# hardware_ProjectFish.net
KiCad netlist of a schematic drawn in Altium Designer
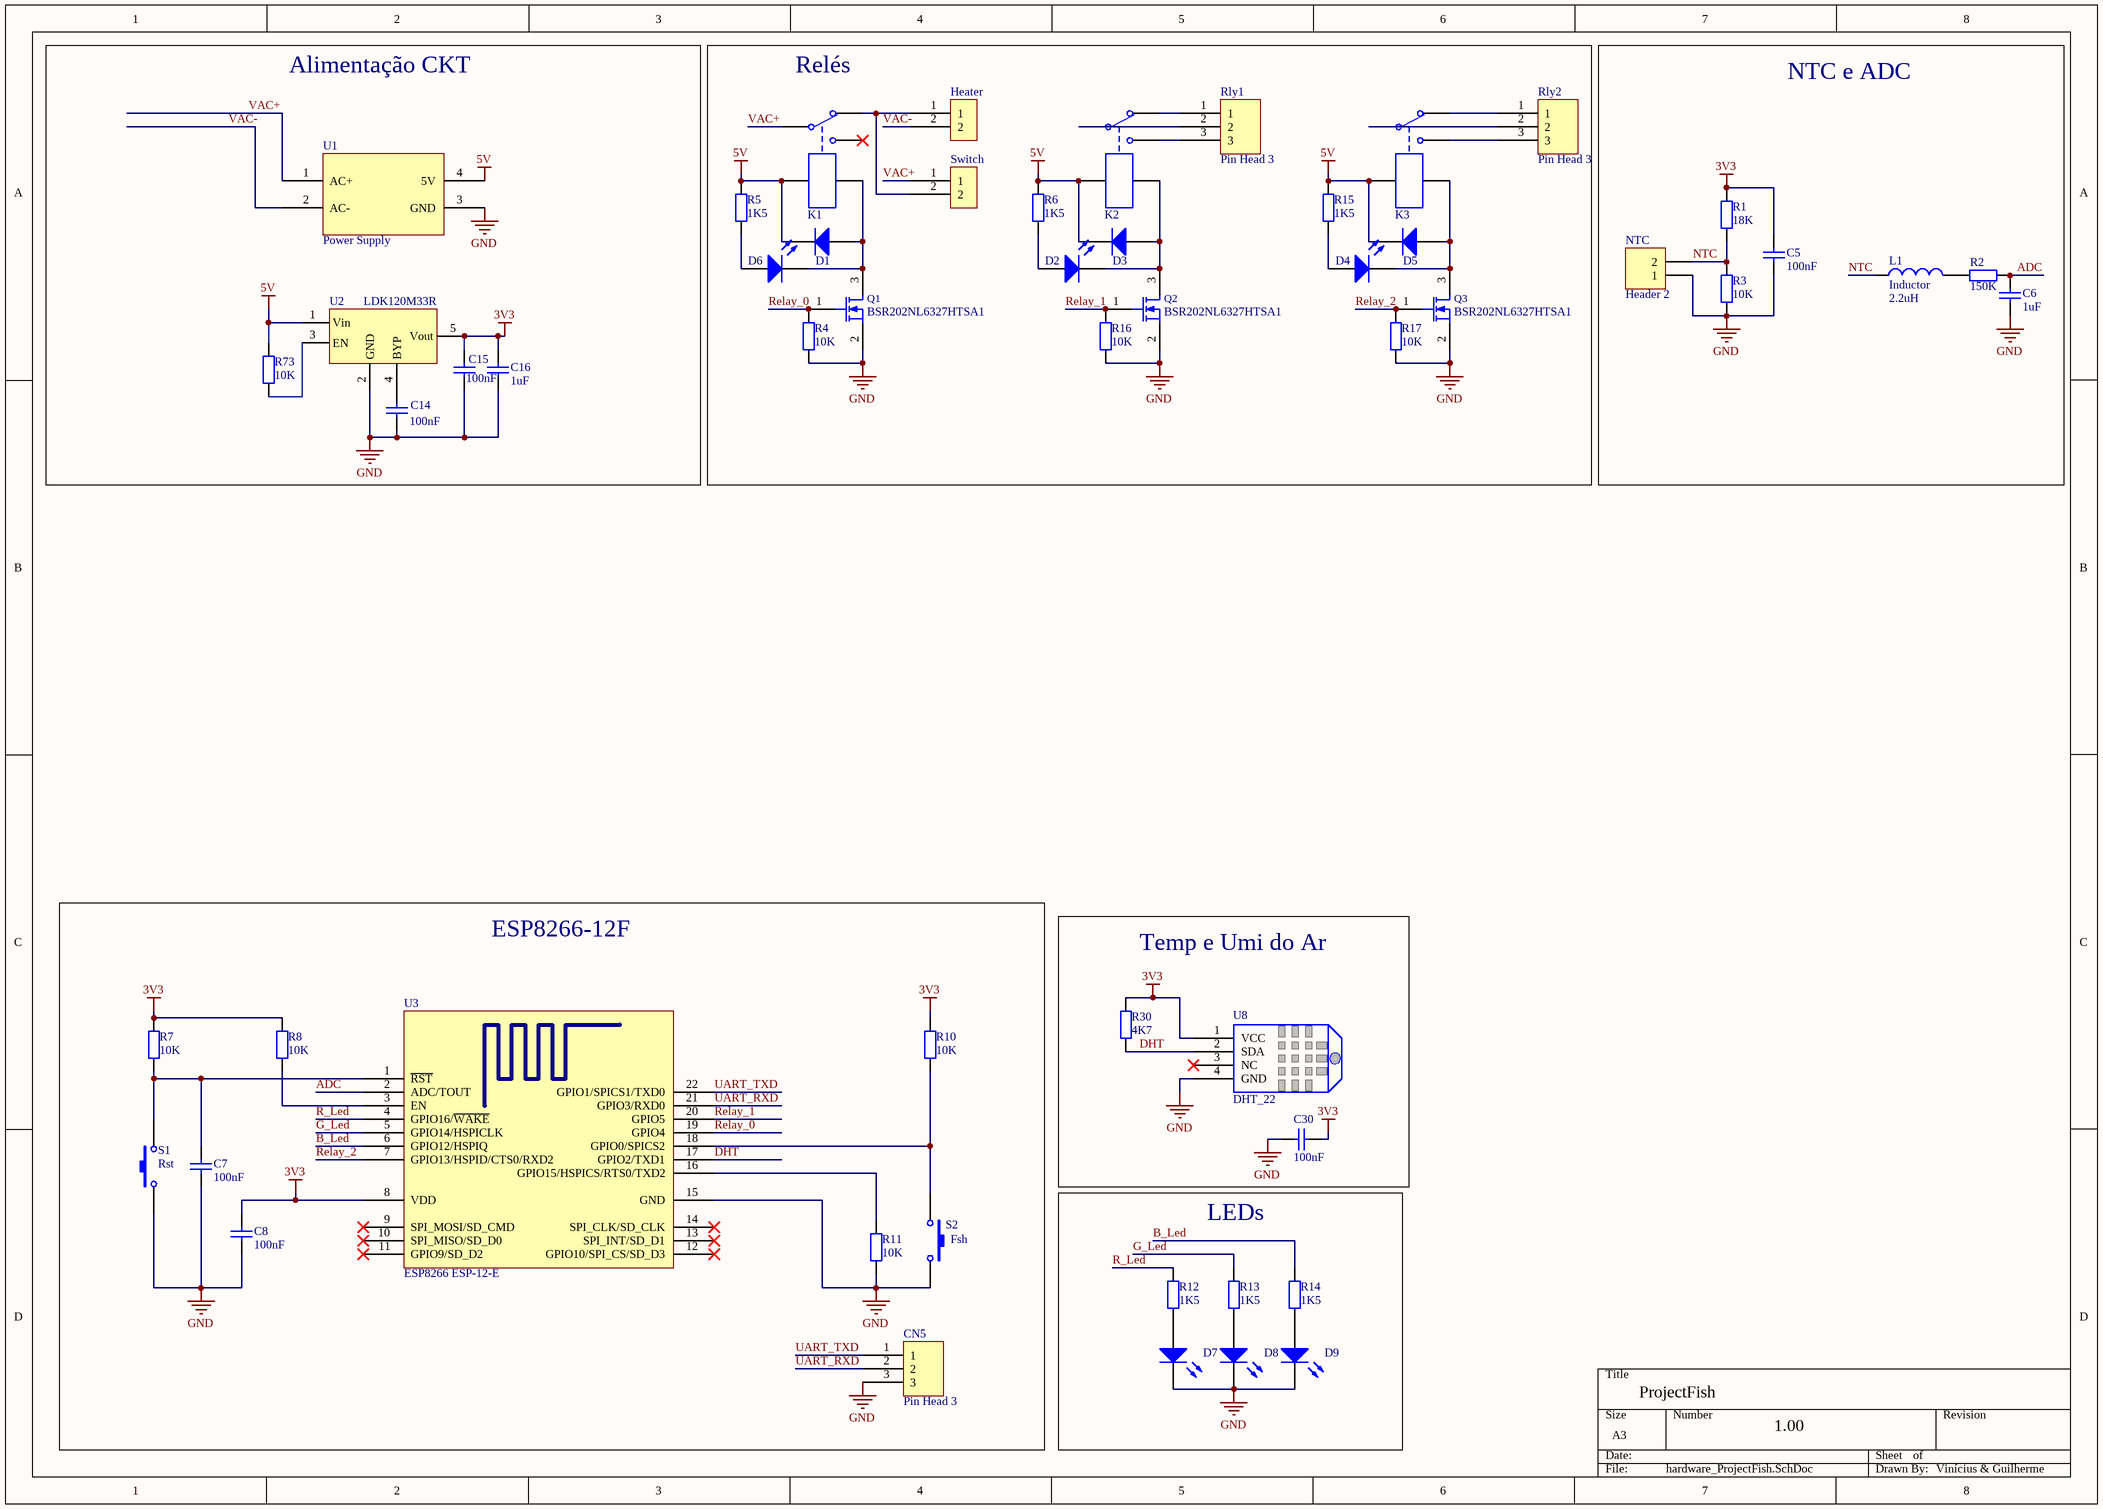
[diagram p0: hardware_ProjectFish.SchDoc]

(export (version "E")
  (design (tool "Eeschema 10.0.6"))
  (components
    (comp (ref "C5")
      (value "100nF")
      (footprint "0805 C")
      (description "Capacitor, ceramic, 100nF, 50V, 0805")
      (fields
        (field (name "PART NUMBER") "RK-cer-100nF-50V-0805")
        (field (name "Comment") "Cap-cer-100nF-50V-0805")
      )
      (libsource (lib "RAKS") (part "Cap-cer-100nF-50V-0805"))
    )
    (comp (ref "C6")
      (value "1uF")
      (footprint "0805 C")
      (description "Capacitor, ceramic, 1uF, 16V, 0805")
      (fields
        (field (name "PART NUMBER") "RK-cer-1uF-16V-0805")
        (field (name "Comment") "Cap-cer-1uF-16V-0805")
      )
      (libsource (lib "RAKS") (part "Cap-cer-1uF-16V-0805"))
    )
    (comp (ref "C7")
      (value "100nF")
      (footprint "0805 C")
      (description "Capacitor, ceramic, 100nF, 50V, 0805")
      (fields
        (field (name "PART NUMBER") "RK-cer-100nF-50V-0805")
        (field (name "Comment") "Cap-cer-100nF-50V-0805")
      )
      (libsource (lib "RAKS") (part "Cap-cer-100nF-50V-0805"))
    )
    (comp (ref "C8")
      (value "100nF")
      (footprint "0805 C")
      (description "Capacitor, ceramic, 100nF, 50V, 0805")
      (fields
        (field (name "PART NUMBER") "RK-cer-100nF-50V-0805")
        (field (name "Comment") "Cap-cer-100nF-50V-0805")
      )
      (libsource (lib "RAKS") (part "Cap-cer-100nF-50V-0805"))
    )
    (comp (ref "C14")
      (value "100nF")
      (footprint "0805 C")
      (description "Capacitor (Semiconductor SIM Model)")
      (fields (field (name "Comment") "Capacitor1") (field (name "PUBLISHER") "Altium Limited"))
      (libsource (lib "RAKS") (part "Capacitor1"))
    )
    (comp (ref "C15")
      (value "100nF")
      (footprint "0805 C")
      (description "Capacitor (Semiconductor SIM Model)")
      (fields (field (name "Comment") "Capacitor1") (field (name "PUBLISHER") "Altium Limited"))
      (libsource (lib "RAKS") (part "Capacitor1"))
    )
    (comp (ref "C16")
      (value "1uF")
      (footprint "0805 C")
      (description "Capacitor (Semiconductor SIM Model)")
      (fields (field (name "Comment") "Capacitor1") (field (name "PUBLISHER") "Altium Limited"))
      (libsource (lib "RAKS") (part "Capacitor1"))
    )
    (comp (ref "C30")
      (value "100nF")
      (footprint "0805 C")
      (description "Capacitor (Semiconductor SIM Model)")
      (fields (field (name "Comment") "Capacitor1") (field (name "PUBLISHER") "Altium Limited"))
      (libsource (lib "RAKS") (part "Capacitor1"))
    )
    (comp (ref "CN5")
      (value "Pin Head 3")
      (footprint "PIN HEAD 3")
      (libsource (lib "RAKS") (part "Pin Head 3"))
    )
    (comp (ref "D1")
      (value "Diode 1N4007")
      (footprint "DO-214AC")
      (description "1 Amp General Purpose Rectifier")
      (fields (field (name "PUBLISHER") "Altium Limited"))
      (libsource (lib "Miscellaneous Devices") (part "Diode 1N4007"))
    )
    (comp (ref "D2") (value "LED") (footprint "0805 LED") (libsource (lib "RAKS") (part "LED")))
    (comp (ref "D3")
      (value "Diode 1N4007")
      (footprint "DO-214AC")
      (description "1 Amp General Purpose Rectifier")
      (fields (field (name "PUBLISHER") "Altium Limited"))
      (libsource (lib "Miscellaneous Devices") (part "Diode 1N4007"))
    )
    (comp (ref "D4") (value "LED") (footprint "0805 LED") (libsource (lib "RAKS") (part "LED")))
    (comp (ref "D5")
      (value "Diode 1N4007")
      (footprint "DO-214AC")
      (description "1 Amp General Purpose Rectifier")
      (fields (field (name "PUBLISHER") "Altium Limited"))
      (libsource (lib "Miscellaneous Devices") (part "Diode 1N4007"))
    )
    (comp (ref "D6") (value "LED") (footprint "0805 LED") (libsource (lib "RAKS") (part "LED")))
    (comp (ref "D7") (value "LED") (footprint "0805 LED") (libsource (lib "RAKS") (part "LED")))
    (comp (ref "D8") (value "LED") (footprint "0805 LED") (libsource (lib "RAKS") (part "LED")))
    (comp (ref "D9") (value "LED") (footprint "0805 LED") (libsource (lib "RAKS") (part "LED")))
    (comp (ref "Heater")
      (value "Pin Head 2")
      (footprint "KRM mini")
      (libsource (lib "RAKS") (part "Pin Head 2"))
    )
    (comp (ref "K1") (value "Relay") (footprint "Relay") (libsource (lib "RAKS") (part "Relay")))
    (comp (ref "K2") (value "Relay") (footprint "Relay") (libsource (lib "RAKS") (part "Relay")))
    (comp (ref "K3") (value "Relay") (footprint "Relay") (libsource (lib "RAKS") (part "Relay")))
    (comp (ref "L1")
      (value "Inductor")
      (footprint "0805 R")
      (fields (field (name "ALTIUM_VALUE") "2.2uH") (field (name "PUBLISHER") "Altium Limited"))
      (libsource (lib "Miscellaneous Devices") (part "Inductor"))
    )
    (comp (ref "NTC")
      (value "Header 2")
      (footprint "HDR1X2")
      (description "Header, 2-Pin")
      (fields (field (name "PUBLISHER") "Altium Limited"))
      (libsource (lib "Miscellaneous Connectors") (part "Header 2"))
    )
    (comp (ref "Q1")
      (value "BSR202NL6327HTSA1")
      (footprint "BSR202NL")
      (description "N-Channel MOSFET")
      (fields (field (name "PUBLISHER") "Altium Limited"))
      (libsource (lib "RAKS") (part "MOSFET-N"))
    )
    (comp (ref "Q2")
      (value "BSR202NL6327HTSA1")
      (footprint "BSR202NL")
      (description "N-Channel MOSFET")
      (fields (field (name "PUBLISHER") "Altium Limited"))
      (libsource (lib "RAKS") (part "MOSFET-N"))
    )
    (comp (ref "Q3")
      (value "BSR202NL6327HTSA1")
      (footprint "BSR202NL")
      (description "N-Channel MOSFET")
      (fields (field (name "PUBLISHER") "Altium Limited"))
      (libsource (lib "RAKS") (part "MOSFET-N"))
    )
    (comp (ref "R1")
      (value "18K")
      (footprint "0805 R")
      (description "Resistor, 18K, 0805, 1%, 1/8W")
      (fields
        (field (name "PART NUMBER") "RK-18K-0805-1%-1/8W")
        (field (name "Comment") "Res-18K-0805-1%-1/8W")
      )
      (libsource (lib "RAKS") (part "Res-18K-0805-1%-1/8W"))
    )
    (comp (ref "R2")
      (value "150K")
      (footprint "0805 R")
      (description "Resistor, 150K, 0805, 1%, 1/8W")
      (fields
        (field (name "PART NUMBER") "RK-150K-0805-1%-1/8W")
        (field (name "Comment") "Res-150K-0805-1%-1/8W")
      )
      (libsource (lib "RAKS") (part "Res-150K-0805-1%-1/8W"))
    )
    (comp (ref "R3")
      (value "10K")
      (footprint "0805 R")
      (description "Resistor, 10K, 0805, 1%, 1/8W")
      (fields
        (field (name "PART NUMBER") "RK-10K-0805-1%-1/8W")
        (field (name "Comment") "Res-10K-0805-1%-1/8W")
      )
      (libsource (lib "RAKS") (part "Res-10K-0805-1%-1/8W"))
    )
    (comp (ref "R4")
      (value "10K")
      (footprint "0805 R")
      (description "Resistor, 10K, 0805, 1%, 1/8W")
      (fields
        (field (name "PART NUMBER") "RK-10K-0805-1%-1/8W")
        (field (name "Comment") "Res-10K-0805-1%-1/8W")
      )
      (libsource (lib "RAKS") (part "Res-10K-0805-1%-1/8W"))
    )
    (comp (ref "R5")
      (value "1K5")
      (footprint "0805 R")
      (description "Resistor, 1K8, 0805, 1%, 1/8W")
      (fields
        (field (name "PART NUMBER") "RK-1K8-0805-1%-1/8W")
        (field (name "Comment") "Res-1K8-0805-1%-1/8W")
      )
      (libsource (lib "RAKS") (part "Res-1K8-0805-1%-1/8W"))
    )
    (comp (ref "R6")
      (value "1K5")
      (footprint "0805 R")
      (description "Resistor, 1K8, 0805, 1%, 1/8W")
      (fields
        (field (name "PART NUMBER") "RK-1K8-0805-1%-1/8W")
        (field (name "Comment") "Res-1K8-0805-1%-1/8W")
      )
      (libsource (lib "RAKS") (part "Res-1K8-0805-1%-1/8W"))
    )
    (comp (ref "R7")
      (value "10K")
      (footprint "0805 R")
      (description "Resistor, 10K, 0805, 1%, 1/8W")
      (fields
        (field (name "PART NUMBER") "RK-10K-0805-1%-1/8W")
        (field (name "Comment") "Res-10K-0805-1%-1/8W")
      )
      (libsource (lib "RAKS") (part "Res-10K-0805-1%-1/8W"))
    )
    (comp (ref "R8")
      (value "10K")
      (footprint "0805 R")
      (description "Resistor, 10K, 0805, 1%, 1/8W")
      (fields
        (field (name "PART NUMBER") "RK-10K-0805-1%-1/8W")
        (field (name "Comment") "Res-10K-0805-1%-1/8W")
      )
      (libsource (lib "RAKS") (part "Res-10K-0805-1%-1/8W"))
    )
    (comp (ref "R10")
      (value "10K")
      (footprint "0805 R")
      (description "Resistor, 10K, 0805, 1%, 1/8W")
      (fields
        (field (name "PART NUMBER") "RK-10K-0805-1%-1/8W")
        (field (name "Comment") "Res-10K-0805-1%-1/8W")
      )
      (libsource (lib "RAKS") (part "Res-10K-0805-1%-1/8W"))
    )
    (comp (ref "R11")
      (value "10K")
      (footprint "0805 R")
      (description "Resistor, 10K, 0805, 1%, 1/8W")
      (fields
        (field (name "PART NUMBER") "RK-10K-0805-1%-1/8W")
        (field (name "Comment") "Res-10K-0805-1%-1/8W")
      )
      (libsource (lib "RAKS") (part "Res-10K-0805-1%-1/8W"))
    )
    (comp (ref "R12")
      (value "1K5")
      (footprint "0805 R")
      (description "Resistor, 1K,5 0805, 1%, 1/8W")
      (fields
        (field (name "PART NUMBER") "RK-1K5-0805-1%-1/8W")
        (field (name "Comment") "Res-1K5-0805-1%-1/8W")
      )
      (libsource (lib "RAKS") (part "Res-1K5-0805-1%-1/8W"))
    )
    (comp (ref "R13")
      (value "1K5")
      (footprint "0805 R")
      (description "Resistor, 1K,5 0805, 1%, 1/8W")
      (fields
        (field (name "PART NUMBER") "RK-1K5-0805-1%-1/8W")
        (field (name "Comment") "Res-1K5-0805-1%-1/8W")
      )
      (libsource (lib "RAKS") (part "Res-1K5-0805-1%-1/8W"))
    )
    (comp (ref "R14")
      (value "1K5")
      (footprint "0805 R")
      (description "Resistor, 1K,5 0805, 1%, 1/8W")
      (fields
        (field (name "PART NUMBER") "RK-1K5-0805-1%-1/8W")
        (field (name "Comment") "Res-1K5-0805-1%-1/8W")
      )
      (libsource (lib "RAKS") (part "Res-1K5-0805-1%-1/8W"))
    )
    (comp (ref "R15")
      (value "1K5")
      (footprint "0805 R")
      (description "Resistor, 1K8, 0805, 1%, 1/8W")
      (fields
        (field (name "PART NUMBER") "RK-1K8-0805-1%-1/8W")
        (field (name "Comment") "Res-1K8-0805-1%-1/8W")
      )
      (libsource (lib "RAKS") (part "Res-1K8-0805-1%-1/8W"))
    )
    (comp (ref "R16")
      (value "10K")
      (footprint "0805 R")
      (description "Resistor, 10K, 0805, 1%, 1/8W")
      (fields
        (field (name "PART NUMBER") "RK-10K-0805-1%-1/8W")
        (field (name "Comment") "Res-10K-0805-1%-1/8W")
      )
      (libsource (lib "RAKS") (part "Res-10K-0805-1%-1/8W"))
    )
    (comp (ref "R17")
      (value "10K")
      (footprint "0805 R")
      (description "Resistor, 10K, 0805, 1%, 1/8W")
      (fields
        (field (name "PART NUMBER") "RK-10K-0805-1%-1/8W")
        (field (name "Comment") "Res-10K-0805-1%-1/8W")
      )
      (libsource (lib "RAKS") (part "Res-10K-0805-1%-1/8W"))
    )
    (comp (ref "R30")
      (value "4K7")
      (footprint "0805 R")
      (description "Resistor")
      (fields (field (name "Comment") "Resistor1") (field (name "PUBLISHER") "Altium Limited"))
      (libsource (lib "RAKS") (part "Resistor1"))
    )
    (comp (ref "R73")
      (value "10K")
      (footprint "0805 R")
      (description "Resistor")
      (fields (field (name "Comment") "Resistor1") (field (name "PUBLISHER") "Altium Limited"))
      (libsource (lib "RAKS") (part "Resistor1"))
    )
    (comp (ref "Rly1") (value "Pin Head 3") (footprint "KRM 3") (libsource (lib "RAKS") (part "Pin Head 3")))
    (comp (ref "Rly2") (value "Pin Head 3") (footprint "KRM 3") (libsource (lib "RAKS") (part "Pin Head 3")))
    (comp (ref "S1")
      (value "Rst")
      (footprint "Button_SMD")
      (description "Switch NA")
      (libsource (lib "RAKS") (part "SW-PB"))
    )
    (comp (ref "S2")
      (value "Fsh")
      (footprint "Button_SMD")
      (description "Switch NA")
      (libsource (lib "RAKS") (part "SW-PB"))
    )
    (comp (ref "Switch")
      (value "Pin Head 2")
      (footprint "KRM mini")
      (libsource (lib "RAKS") (part "Pin Head 2"))
    )
    (comp (ref "U1")
      (value "Power Supply")
      (footprint "Sanmim SM-PLF12B")
      (description "AC/DC switch 5V@2A power supply")
      (libsource (lib "RAKS") (part "SANMIM SM-PLF12B"))
    )
    (comp (ref "U2")
      (value "LDK120M33R")
      (footprint "SOT-23-5")
      (description "Voltage Regulator")
      (libsource (lib "RAKS") (part "LDK120M33R"))
    )
    (comp (ref "U3")
      (value "ESP8266 ESP-12-E")
      (footprint "RAKS:ESP8266 ESP-12-E")
      (libsource (lib "RAKS") (part "ESP8266 ESP-12-E"))
    )
    (comp (ref "U8") (value "DHT_22") (footprint "Pin Head 4") (libsource (lib "RAKS") (part "DHT_22")))
  )
  (nets
    (net (code "1") (name "/ADC") (class "Default")
      (node (ref "C6") (pin "2") (pinfunction "2_2") (pintype "passive"))
      (node (ref "R2") (pin "2") (pinfunction "2_2") (pintype "passive"))
      (node (ref "U3") (pin "2") (pinfunction "ADC/TOUT_2") (pintype "passive"))
    )
    (net (code "2") (name "/B_Led") (class "Default")
      (node (ref "R14") (pin "2") (pinfunction "2_2") (pintype "passive"))
      (node (ref "U3") (pin "6") (pinfunction "GPIO12/HSPIQ_6") (pintype "passive"))
    )
    (net (code "3") (name "/DHT") (class "Default")
      (node (ref "R30") (pin "2") (pinfunction "2_2") (pintype "passive"))
      (node (ref "U3") (pin "17") (pinfunction "GPIO2/TXD1_17") (pintype "passive"))
      (node (ref "U8") (pin "2") (pinfunction "SDA_2") (pintype "passive"))
    )
    (net (code "4") (name "/G_Led") (class "Default")
      (node (ref "R13") (pin "2") (pinfunction "2_2") (pintype "passive"))
      (node (ref "U3") (pin "5") (pinfunction "GPIO14/HSPICLK_5") (pintype "passive"))
    )
    (net (code "5") (name "/NTC") (class "Default")
      (node (ref "L1") (pin "1") (pinfunction "1_1") (pintype "passive"))
      (node (ref "NTC") (pin "2") (pinfunction "2_2") (pintype "passive"))
      (node (ref "R1") (pin "1") (pinfunction "1_1") (pintype "passive"))
      (node (ref "R3") (pin "2") (pinfunction "2_2") (pintype "passive"))
    )
    (net (code "6") (name "/R_Led") (class "Default")
      (node (ref "R12") (pin "2") (pinfunction "2_2") (pintype "passive"))
      (node (ref "U3") (pin "4") (pinfunction "GPIO16/~{WAKE}_4") (pintype "passive"))
    )
    (net (code "7") (name "/Relay_0") (class "Default")
      (node (ref "Q1") (pin "1") (pinfunction "G_1") (pintype "passive"))
      (node (ref "R4") (pin "2") (pinfunction "2_2") (pintype "passive"))
      (node (ref "U3") (pin "19") (pinfunction "GPIO4_19") (pintype "passive"))
    )
    (net (code "8") (name "/Relay_1") (class "Default")
      (node (ref "Q2") (pin "1") (pinfunction "G_1") (pintype "passive"))
      (node (ref "R16") (pin "2") (pinfunction "2_2") (pintype "passive"))
      (node (ref "U3") (pin "20") (pinfunction "GPIO5_20") (pintype "passive"))
    )
    (net (code "9") (name "/Relay_2") (class "Default")
      (node (ref "Q3") (pin "1") (pinfunction "G_1") (pintype "passive"))
      (node (ref "R17") (pin "2") (pinfunction "2_2") (pintype "passive"))
      (node (ref "U3") (pin "7") (pinfunction "GPIO13/HSPID/CTS0/RXD2_7") (pintype "passive"))
    )
    (net (code "10") (name "/UART_RXD") (class "Default")
      (node (ref "CN5") (pin "2") (pinfunction "2_2") (pintype "passive"))
      (node (ref "U3") (pin "21") (pinfunction "GPIO3/RXD0_21") (pintype "passive"))
    )
    (net (code "11") (name "/UART_TXD") (class "Default")
      (node (ref "CN5") (pin "1") (pinfunction "1_1") (pintype "passive"))
      (node (ref "U3") (pin "22") (pinfunction "GPIO1/SPICS1/TXD0_22") (pintype "passive"))
    )
    (net (code "12") (name "/VAC+") (class "Default")
      (node (ref "K1") (pin "1") (pinfunction "1_1") (pintype "passive"))
      (node (ref "Switch") (pin "1") (pinfunction "1_1") (pintype "passive"))
      (node (ref "U1") (pin "1") (pinfunction "AC+_1") (pintype "passive"))
    )
    (net (code "13") (name "/VAC-") (class "Default")
      (node (ref "Heater") (pin "2") (pinfunction "2_2") (pintype "passive"))
      (node (ref "U1") (pin "2") (pinfunction "AC-_2") (pintype "passive"))
    )
    (net (code "14") (name "3V3") (class "Default")
      (node (ref "C15") (pin "2") (pinfunction "2_2") (pintype "passive"))
      (node (ref "C16") (pin "2") (pinfunction "2_2") (pintype "passive"))
      (node (ref "C30") (pin "2") (pinfunction "2_2") (pintype "passive"))
      (node (ref "C5") (pin "1") (pinfunction "1_1") (pintype "passive"))
      (node (ref "C8") (pin "1") (pinfunction "1_1") (pintype "passive"))
      (node (ref "R1") (pin "2") (pinfunction "2_2") (pintype "passive"))
      (node (ref "R10") (pin "2") (pinfunction "2_2") (pintype "passive"))
      (node (ref "R30") (pin "1") (pinfunction "1_1") (pintype "passive"))
      (node (ref "R7") (pin "2") (pinfunction "2_2") (pintype "passive"))
      (node (ref "R8") (pin "2") (pinfunction "2_2") (pintype "passive"))
      (node (ref "U2") (pin "5") (pinfunction "Vout_5") (pintype "passive"))
      (node (ref "U3") (pin "8") (pinfunction "VDD_8") (pintype "passive"))
      (node (ref "U8") (pin "1") (pinfunction "VCC_1") (pintype "passive"))
    )
    (net (code "15") (name "5V") (class "Default")
      (node (ref "D1") (pin "2") (pinfunction "K_2") (pintype "passive"))
      (node (ref "D3") (pin "2") (pinfunction "K_2") (pintype "passive"))
      (node (ref "D5") (pin "2") (pinfunction "K_2") (pintype "passive"))
      (node (ref "K1") (pin "4") (pinfunction "4_4") (pintype "passive"))
      (node (ref "K2") (pin "4") (pinfunction "4_4") (pintype "passive"))
      (node (ref "K3") (pin "4") (pinfunction "4_4") (pintype "passive"))
      (node (ref "R15") (pin "2") (pinfunction "2_2") (pintype "passive"))
      (node (ref "R5") (pin "2") (pinfunction "2_2") (pintype "passive"))
      (node (ref "R6") (pin "2") (pinfunction "2_2") (pintype "passive"))
      (node (ref "R73") (pin "1") (pinfunction "1_1") (pintype "passive"))
      (node (ref "U1") (pin "4") (pinfunction "5V_4") (pintype "passive"))
      (node (ref "U2") (pin "1") (pinfunction "Vin_1") (pintype "passive"))
    )
    (net (code "16") (name "GND") (class "Default")
      (node (ref "C14") (pin "1") (pinfunction "1_1") (pintype "passive"))
      (node (ref "C15") (pin "1") (pinfunction "1_1") (pintype "passive"))
      (node (ref "C16") (pin "1") (pinfunction "1_1") (pintype "passive"))
      (node (ref "C30") (pin "1") (pinfunction "1_1") (pintype "passive"))
      (node (ref "C5") (pin "2") (pinfunction "2_2") (pintype "passive"))
      (node (ref "C6") (pin "1") (pinfunction "1_1") (pintype "passive"))
      (node (ref "C7") (pin "1") (pinfunction "1_1") (pintype "passive"))
      (node (ref "C8") (pin "2") (pinfunction "2_2") (pintype "passive"))
      (node (ref "CN5") (pin "3") (pinfunction "3_3") (pintype "passive"))
      (node (ref "D7") (pin "2") (pinfunction "K_2") (pintype "passive"))
      (node (ref "D8") (pin "2") (pinfunction "K_2") (pintype "passive"))
      (node (ref "D9") (pin "2") (pinfunction "K_2") (pintype "passive"))
      (node (ref "NTC") (pin "1") (pinfunction "1_1") (pintype "passive"))
      (node (ref "Q1") (pin "2") (pinfunction "S_2") (pintype "passive"))
      (node (ref "Q2") (pin "2") (pinfunction "S_2") (pintype "passive"))
      (node (ref "Q3") (pin "2") (pinfunction "S_2") (pintype "passive"))
      (node (ref "R11") (pin "1") (pinfunction "1_1") (pintype "passive"))
      (node (ref "R16") (pin "1") (pinfunction "1_1") (pintype "passive"))
      (node (ref "R17") (pin "1") (pinfunction "1_1") (pintype "passive"))
      (node (ref "R3") (pin "1") (pinfunction "1_1") (pintype "passive"))
      (node (ref "R4") (pin "1") (pinfunction "1_1") (pintype "passive"))
      (node (ref "S1") (pin "1") (pinfunction "1_1") (pintype "passive"))
      (node (ref "S2") (pin "1") (pinfunction "1_1") (pintype "passive"))
      (node (ref "U1") (pin "3") (pinfunction "GND_3") (pintype "passive"))
      (node (ref "U2") (pin "2") (pinfunction "GND_2") (pintype "passive"))
      (node (ref "U3") (pin "15") (pinfunction "GND_15") (pintype "passive"))
      (node (ref "U8") (pin "4") (pinfunction "GND_4") (pintype "passive"))
    )
    (net (code "17") (name "Net-(D1-A)") (class "Default")
      (node (ref "D1") (pin "1") (pinfunction "A_1") (pintype "passive"))
      (node (ref "D6") (pin "2") (pinfunction "K_2") (pintype "passive"))
      (node (ref "K1") (pin "5") (pinfunction "5_5") (pintype "passive"))
      (node (ref "Q1") (pin "3") (pinfunction "D_3") (pintype "passive"))
    )
    (net (code "18") (name "Net-(D2-A)") (class "Default")
      (node (ref "D2") (pin "1") (pinfunction "A_1") (pintype "passive"))
      (node (ref "R6") (pin "1") (pinfunction "1_1") (pintype "passive"))
    )
    (net (code "19") (name "Net-(D2-K)") (class "Default")
      (node (ref "D2") (pin "2") (pinfunction "K_2") (pintype "passive"))
      (node (ref "D3") (pin "1") (pinfunction "A_1") (pintype "passive"))
      (node (ref "K2") (pin "5") (pinfunction "5_5") (pintype "passive"))
      (node (ref "Q2") (pin "3") (pinfunction "D_3") (pintype "passive"))
    )
    (net (code "20") (name "Net-(D4-A)") (class "Default")
      (node (ref "D4") (pin "1") (pinfunction "A_1") (pintype "passive"))
      (node (ref "R15") (pin "1") (pinfunction "1_1") (pintype "passive"))
    )
    (net (code "21") (name "Net-(D4-K)") (class "Default")
      (node (ref "D4") (pin "2") (pinfunction "K_2") (pintype "passive"))
      (node (ref "D5") (pin "1") (pinfunction "A_1") (pintype "passive"))
      (node (ref "K3") (pin "5") (pinfunction "5_5") (pintype "passive"))
      (node (ref "Q3") (pin "3") (pinfunction "D_3") (pintype "passive"))
    )
    (net (code "22") (name "Net-(D6-A)") (class "Default")
      (node (ref "D6") (pin "1") (pinfunction "A_1") (pintype "passive"))
      (node (ref "R5") (pin "1") (pinfunction "1_1") (pintype "passive"))
    )
    (net (code "23") (name "Net-(D7-A)") (class "Default")
      (node (ref "D7") (pin "1") (pinfunction "A_1") (pintype "passive"))
      (node (ref "R12") (pin "1") (pinfunction "1_1") (pintype "passive"))
    )
    (net (code "24") (name "Net-(D8-A)") (class "Default")
      (node (ref "D8") (pin "1") (pinfunction "A_1") (pintype "passive"))
      (node (ref "R13") (pin "1") (pinfunction "1_1") (pintype "passive"))
    )
    (net (code "25") (name "Net-(D9-A)") (class "Default")
      (node (ref "D9") (pin "1") (pinfunction "A_1") (pintype "passive"))
      (node (ref "R14") (pin "1") (pinfunction "1_1") (pintype "passive"))
    )
    (net (code "26") (name "Net-(Heater-Pad1)") (class "Default")
      (node (ref "Heater") (pin "1") (pinfunction "1_1") (pintype "passive"))
      (node (ref "K1") (pin "2") (pinfunction "2_2") (pintype "passive"))
      (node (ref "Switch") (pin "2") (pinfunction "2_2") (pintype "passive"))
    )
    (net (code "27") (name "Net-(K2-Pad1)") (class "Default")
      (node (ref "K2") (pin "1") (pinfunction "1_1") (pintype "passive"))
      (node (ref "Rly1") (pin "2") (pinfunction "2_2") (pintype "passive"))
    )
    (net (code "28") (name "Net-(K2-Pad2)") (class "Default")
      (node (ref "K2") (pin "2") (pinfunction "2_2") (pintype "passive"))
      (node (ref "Rly1") (pin "1") (pinfunction "1_1") (pintype "passive"))
    )
    (net (code "29") (name "Net-(K2-Pad3)") (class "Default")
      (node (ref "K2") (pin "3") (pinfunction "3_3") (pintype "passive"))
      (node (ref "Rly1") (pin "3") (pinfunction "3_3") (pintype "passive"))
    )
    (net (code "30") (name "Net-(K3-Pad1)") (class "Default")
      (node (ref "K3") (pin "1") (pinfunction "1_1") (pintype "passive"))
      (node (ref "Rly2") (pin "2") (pinfunction "2_2") (pintype "passive"))
    )
    (net (code "31") (name "Net-(K3-Pad2)") (class "Default")
      (node (ref "K3") (pin "2") (pinfunction "2_2") (pintype "passive"))
      (node (ref "Rly2") (pin "1") (pinfunction "1_1") (pintype "passive"))
    )
    (net (code "32") (name "Net-(K3-Pad3)") (class "Default")
      (node (ref "K3") (pin "3") (pinfunction "3_3") (pintype "passive"))
      (node (ref "Rly2") (pin "3") (pinfunction "3_3") (pintype "passive"))
    )
    (net (code "33") (name "Net-(L1-Pad2)") (class "Default")
      (node (ref "L1") (pin "2") (pinfunction "2_2") (pintype "passive"))
      (node (ref "R2") (pin "1") (pinfunction "1_1") (pintype "passive"))
    )
    (net (code "34") (name "Net-(U2-BYP)") (class "Default")
      (node (ref "C14") (pin "2") (pinfunction "2_2") (pintype "passive"))
      (node (ref "U2") (pin "4") (pinfunction "BYP_4") (pintype "passive"))
    )
    (net (code "35") (name "Net-(U2-EN)") (class "Default")
      (node (ref "R73") (pin "2") (pinfunction "2_2") (pintype "passive"))
      (node (ref "U2") (pin "3") (pinfunction "EN_3") (pintype "passive"))
    )
    (net (code "36") (name "Net-(U3-EN)") (class "Default")
      (node (ref "R8") (pin "1") (pinfunction "1_1") (pintype "passive"))
      (node (ref "U3") (pin "3") (pinfunction "EN_3") (pintype "passive"))
    )
    (net (code "37") (name "Net-(U3-GPIO0{slash}SPICS2)") (class "Default")
      (node (ref "R10") (pin "1") (pinfunction "1_1") (pintype "passive"))
      (node (ref "S2") (pin "2") (pinfunction "2_2") (pintype "passive"))
      (node (ref "U3") (pin "18") (pinfunction "GPIO0/SPICS2_18") (pintype "passive"))
    )
    (net (code "38") (name "Net-(U3-GPIO15{slash}HSPICS{slash}RTS0{slash}TXD2)") (class "Default")
      (node (ref "R11") (pin "2") (pinfunction "2_2") (pintype "passive"))
      (node (ref "U3") (pin "16") (pinfunction "GPIO15/HSPICS/RTS0/TXD2_16") (pintype "passive"))
    )
    (net (code "39") (name "Net-(U3-~{RST})") (class "Default")
      (node (ref "C7") (pin "2") (pinfunction "2_2") (pintype "passive"))
      (node (ref "R7") (pin "1") (pinfunction "1_1") (pintype "passive"))
      (node (ref "S1") (pin "2") (pinfunction "2_2") (pintype "passive"))
      (node (ref "U3") (pin "1") (pinfunction "~{RST}_1") (pintype "passive"))
    )
    (net (code "40") (name "unconnected-(K1-Pad3)") (class "Default")
      (node (ref "K1") (pin "3") (pinfunction "3_3") (pintype "passive+no_connect"))
    )
    (net (code "41") (name "unconnected-(U3-GPIO9{slash}SD_D2-Pad11)") (class "Default")
      (node (ref "U3") (pin "11") (pinfunction "GPIO9/SD_D2_11") (pintype "passive+no_connect"))
    )
    (net (code "42") (name "unconnected-(U3-GPIO10{slash}SPI_CS{slash}SD_D3-Pad12)") (class "Default")
      (node (ref "U3") (pin "12") (pinfunction "GPIO10/SPI_CS/SD_D3_12") (pintype "passive+no_connect"))
    )
    (net (code "43") (name "unconnected-(U3-SPI_CLK{slash}SD_CLK-Pad14)") (class "Default")
      (node (ref "U3") (pin "14") (pinfunction "SPI_CLK/SD_CLK_14") (pintype "passive+no_connect"))
    )
    (net (code "44") (name "unconnected-(U3-SPI_INT{slash}SD_D1-Pad13)") (class "Default")
      (node (ref "U3") (pin "13") (pinfunction "SPI_INT/SD_D1_13") (pintype "passive+no_connect"))
    )
    (net (code "45") (name "unconnected-(U3-SPI_MISO{slash}SD_D0-Pad10)") (class "Default")
      (node (ref "U3") (pin "10") (pinfunction "SPI_MISO/SD_D0_10") (pintype "passive+no_connect"))
    )
    (net (code "46") (name "unconnected-(U3-SPI_MOSI{slash}SD_CMD-Pad9)") (class "Default")
      (node (ref "U3") (pin "9") (pinfunction "SPI_MOSI/SD_CMD_9") (pintype "passive+no_connect"))
    )
    (net (code "47") (name "unconnected-(U8-NC-Pad3)") (class "Default")
      (node (ref "U8") (pin "3") (pinfunction "NC_3") (pintype "passive+no_connect"))
    )
  )
)
